# BD0005.net
KiCad netlist of a schematic drawn in EAGLE
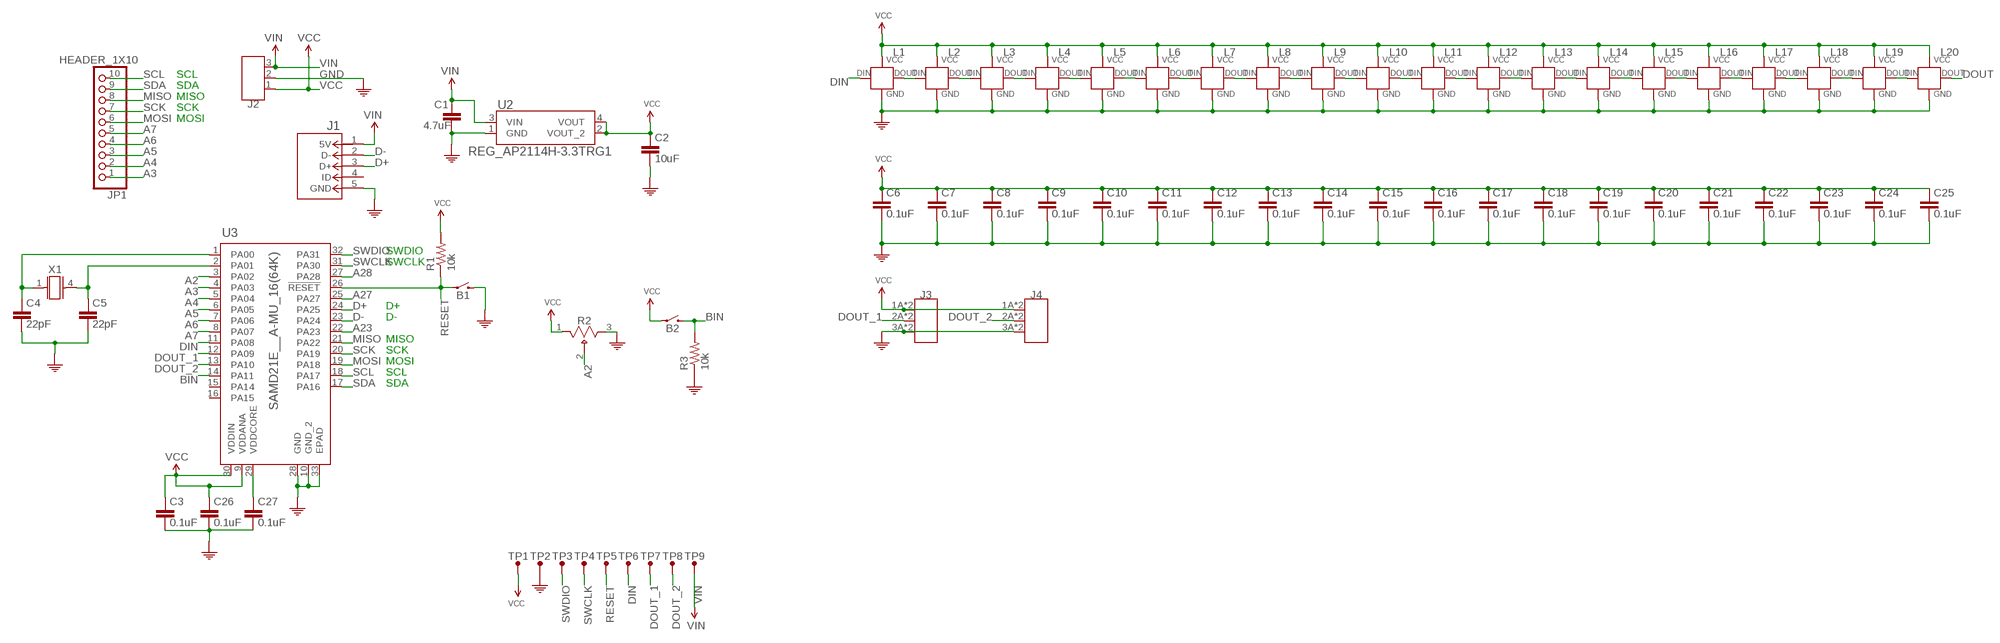
[diagram p0: schematic, sheet 1]

(export (version "E")
  (design (tool "Eeschema 10.0.6"))
  (components
    (comp (ref "B1")
      (value "SWITCH_EVQ-P7A01P")
      (footprint "eagle-import:4-SMD_BUTTON")
      (libsource (lib "eagle-import") (part "SWITCH_EVQ-P7A01P"))
    )
    (comp (ref "B2")
      (value "SWITCH_EVQ-P7A01P")
      (footprint "eagle-import:4-SMD_BUTTON")
      (libsource (lib "eagle-import") (part "SWITCH_EVQ-P7A01P"))
    )
    (comp (ref "C1")
      (value "4.7uF")
      (footprint "eagle-import:0402")
      (libsource (lib "eagle-import") (part "CAPACITOR-0402"))
    )
    (comp (ref "C2")
      (value "10uF")
      (footprint "eagle-import:0402")
      (libsource (lib "eagle-import") (part "CAPACITOR-0402"))
    )
    (comp (ref "C3")
      (value "0.1uF")
      (footprint "eagle-import:0402")
      (libsource (lib "eagle-import") (part "CAPACITOR-0402"))
    )
    (comp (ref "C4")
      (value "22pF")
      (footprint "eagle-import:0402")
      (libsource (lib "eagle-import") (part "CAPACITOR-0402"))
    )
    (comp (ref "C5")
      (value "22pF")
      (footprint "eagle-import:0402")
      (libsource (lib "eagle-import") (part "CAPACITOR-0402"))
    )
    (comp (ref "C6")
      (value "0.1uF")
      (footprint "eagle-import:0402")
      (libsource (lib "eagle-import") (part "CAPACITOR-0402"))
    )
    (comp (ref "C7")
      (value "0.1uF")
      (footprint "eagle-import:0402")
      (libsource (lib "eagle-import") (part "CAPACITOR-0402"))
    )
    (comp (ref "C8")
      (value "0.1uF")
      (footprint "eagle-import:0402")
      (libsource (lib "eagle-import") (part "CAPACITOR-0402"))
    )
    (comp (ref "C9")
      (value "0.1uF")
      (footprint "eagle-import:0402")
      (libsource (lib "eagle-import") (part "CAPACITOR-0402"))
    )
    (comp (ref "C10")
      (value "0.1uF")
      (footprint "eagle-import:0402")
      (libsource (lib "eagle-import") (part "CAPACITOR-0402"))
    )
    (comp (ref "C11")
      (value "0.1uF")
      (footprint "eagle-import:0402")
      (libsource (lib "eagle-import") (part "CAPACITOR-0402"))
    )
    (comp (ref "C12")
      (value "0.1uF")
      (footprint "eagle-import:0402")
      (libsource (lib "eagle-import") (part "CAPACITOR-0402"))
    )
    (comp (ref "C13")
      (value "0.1uF")
      (footprint "eagle-import:0402")
      (libsource (lib "eagle-import") (part "CAPACITOR-0402"))
    )
    (comp (ref "C14")
      (value "0.1uF")
      (footprint "eagle-import:0402")
      (libsource (lib "eagle-import") (part "CAPACITOR-0402"))
    )
    (comp (ref "C15")
      (value "0.1uF")
      (footprint "eagle-import:0402")
      (libsource (lib "eagle-import") (part "CAPACITOR-0402"))
    )
    (comp (ref "C16")
      (value "0.1uF")
      (footprint "eagle-import:0402")
      (libsource (lib "eagle-import") (part "CAPACITOR-0402"))
    )
    (comp (ref "C17")
      (value "0.1uF")
      (footprint "eagle-import:0402")
      (libsource (lib "eagle-import") (part "CAPACITOR-0402"))
    )
    (comp (ref "C18")
      (value "0.1uF")
      (footprint "eagle-import:0402")
      (libsource (lib "eagle-import") (part "CAPACITOR-0402"))
    )
    (comp (ref "C19")
      (value "0.1uF")
      (footprint "eagle-import:0402")
      (libsource (lib "eagle-import") (part "CAPACITOR-0402"))
    )
    (comp (ref "C20")
      (value "0.1uF")
      (footprint "eagle-import:0402")
      (libsource (lib "eagle-import") (part "CAPACITOR-0402"))
    )
    (comp (ref "C21")
      (value "0.1uF")
      (footprint "eagle-import:0402")
      (libsource (lib "eagle-import") (part "CAPACITOR-0402"))
    )
    (comp (ref "C22")
      (value "0.1uF")
      (footprint "eagle-import:0402")
      (libsource (lib "eagle-import") (part "CAPACITOR-0402"))
    )
    (comp (ref "C23")
      (value "0.1uF")
      (footprint "eagle-import:0402")
      (libsource (lib "eagle-import") (part "CAPACITOR-0402"))
    )
    (comp (ref "C24")
      (value "0.1uF")
      (footprint "eagle-import:0402")
      (libsource (lib "eagle-import") (part "CAPACITOR-0402"))
    )
    (comp (ref "C25")
      (value "0.1uF")
      (footprint "eagle-import:0402")
      (libsource (lib "eagle-import") (part "CAPACITOR-0402"))
    )
    (comp (ref "C26")
      (value "0.1uF")
      (footprint "eagle-import:0402")
      (libsource (lib "eagle-import") (part "CAPACITOR-0402"))
    )
    (comp (ref "C27")
      (value "0.1uF")
      (footprint "eagle-import:0402")
      (libsource (lib "eagle-import") (part "CAPACITOR-0402"))
    )
    (comp (ref "J1")
      (value "CONN_MICROUSB_FEMALE")
      (footprint "eagle-import:CON00679_5")
      (libsource (lib "eagle-import") (part "CONN_MICROUSB_FEMALE"))
    )
    (comp (ref "J2")
      (value "HEADER_1X3")
      (footprint "eagle-import:1X03-CLEANBIG")
      (libsource (lib "eagle-import") (part "HEADER_1X3"))
    )
    (comp (ref "J3")
      (value "HEADER_1X3FEMALE")
      (footprint "eagle-import:F3SMD_RIGHTANGLE")
      (libsource (lib "eagle-import") (part "HEADER_1X3FEMALE"))
    )
    (comp (ref "J4")
      (value "HEADER_1X3FEMALE")
      (footprint "eagle-import:F3SMD_RIGHTANGLE")
      (libsource (lib "eagle-import") (part "HEADER_1X3FEMALE"))
    )
    (comp (ref "JP1")
      (value "HEADER_1X10")
      (footprint "eagle-import:1X10-BIG")
      (libsource (lib "eagle-import") (part "HEADER_1X10"))
    )
    (comp (ref "L1")
      (value "WS2812B-B")
      (footprint "eagle-import:SK6812-B")
      (libsource (lib "eagle-import") (part "WS2812B-B"))
    )
    (comp (ref "L2")
      (value "WS2812B-B")
      (footprint "eagle-import:SK6812-B")
      (libsource (lib "eagle-import") (part "WS2812B-B"))
    )
    (comp (ref "L3")
      (value "WS2812B-B")
      (footprint "eagle-import:SK6812-B")
      (libsource (lib "eagle-import") (part "WS2812B-B"))
    )
    (comp (ref "L4")
      (value "WS2812B-B")
      (footprint "eagle-import:SK6812-B")
      (libsource (lib "eagle-import") (part "WS2812B-B"))
    )
    (comp (ref "L5")
      (value "WS2812B-B")
      (footprint "eagle-import:SK6812-B")
      (libsource (lib "eagle-import") (part "WS2812B-B"))
    )
    (comp (ref "L6")
      (value "WS2812B-B")
      (footprint "eagle-import:SK6812-B")
      (libsource (lib "eagle-import") (part "WS2812B-B"))
    )
    (comp (ref "L7")
      (value "WS2812B-B")
      (footprint "eagle-import:SK6812-B")
      (libsource (lib "eagle-import") (part "WS2812B-B"))
    )
    (comp (ref "L8")
      (value "WS2812B-B")
      (footprint "eagle-import:SK6812-B")
      (libsource (lib "eagle-import") (part "WS2812B-B"))
    )
    (comp (ref "L9")
      (value "WS2812B-B")
      (footprint "eagle-import:SK6812-B")
      (libsource (lib "eagle-import") (part "WS2812B-B"))
    )
    (comp (ref "L10")
      (value "WS2812B-B")
      (footprint "eagle-import:SK6812-B")
      (libsource (lib "eagle-import") (part "WS2812B-B"))
    )
    (comp (ref "L11")
      (value "WS2812B-B")
      (footprint "eagle-import:SK6812-B")
      (libsource (lib "eagle-import") (part "WS2812B-B"))
    )
    (comp (ref "L12")
      (value "WS2812B-B")
      (footprint "eagle-import:SK6812-B")
      (libsource (lib "eagle-import") (part "WS2812B-B"))
    )
    (comp (ref "L13")
      (value "WS2812B-B")
      (footprint "eagle-import:SK6812-B")
      (libsource (lib "eagle-import") (part "WS2812B-B"))
    )
    (comp (ref "L14")
      (value "WS2812B-B")
      (footprint "eagle-import:SK6812-B")
      (libsource (lib "eagle-import") (part "WS2812B-B"))
    )
    (comp (ref "L15")
      (value "WS2812B-B")
      (footprint "eagle-import:SK6812-B")
      (libsource (lib "eagle-import") (part "WS2812B-B"))
    )
    (comp (ref "L16")
      (value "WS2812B-B")
      (footprint "eagle-import:SK6812-B")
      (libsource (lib "eagle-import") (part "WS2812B-B"))
    )
    (comp (ref "L17")
      (value "WS2812B-B")
      (footprint "eagle-import:SK6812-B")
      (libsource (lib "eagle-import") (part "WS2812B-B"))
    )
    (comp (ref "L18")
      (value "WS2812B-B")
      (footprint "eagle-import:SK6812-B")
      (libsource (lib "eagle-import") (part "WS2812B-B"))
    )
    (comp (ref "L19")
      (value "WS2812B-B")
      (footprint "eagle-import:SK6812-B")
      (libsource (lib "eagle-import") (part "WS2812B-B"))
    )
    (comp (ref "L20")
      (value "WS2812B-B")
      (footprint "eagle-import:SK6812-B")
      (libsource (lib "eagle-import") (part "WS2812B-B"))
    )
    (comp (ref "R1")
      (value "10k")
      (footprint "eagle-import:0402")
      (libsource (lib "eagle-import") (part "RESISTOR-0402"))
    )
    (comp (ref "R2")
      (value "POT_THUMBWHEEL_3352T-1-104LF")
      (footprint "eagle-import:THUMBWHEEL")
      (libsource (lib "eagle-import") (part "POT_THUMBWHEEL_3352T-1-104LF"))
    )
    (comp (ref "R3")
      (value "10k")
      (footprint "eagle-import:0402")
      (libsource (lib "eagle-import") (part "RESISTOR-0402"))
    )
    (comp (ref "TP1")
      (value "VCC")
      (footprint "eagle-import:TEST_POINT")
      (libsource (lib "eagle-import") (part "TEST_POINT"))
    )
    (comp (ref "TP2")
      (value "GND")
      (footprint "eagle-import:TEST_POINT")
      (libsource (lib "eagle-import") (part "TEST_POINT"))
    )
    (comp (ref "TP3")
      (value "DIO")
      (footprint "eagle-import:TEST_POINT")
      (libsource (lib "eagle-import") (part "TEST_POINT"))
    )
    (comp (ref "TP4")
      (value "CLK")
      (footprint "eagle-import:TEST_POINT")
      (libsource (lib "eagle-import") (part "TEST_POINT"))
    )
    (comp (ref "TP5")
      (value "RST")
      (footprint "eagle-import:TEST_POINT")
      (libsource (lib "eagle-import") (part "TEST_POINT"))
    )
    (comp (ref "TP6")
      (value "DIN")
      (footprint "eagle-import:TEST_POINT")
      (libsource (lib "eagle-import") (part "TEST_POINT"))
    )
    (comp (ref "TP7")
      (value "DO1")
      (footprint "eagle-import:TEST_POINT")
      (libsource (lib "eagle-import") (part "TEST_POINT"))
    )
    (comp (ref "TP8")
      (value "DO2")
      (footprint "eagle-import:TEST_POINT")
      (libsource (lib "eagle-import") (part "TEST_POINT"))
    )
    (comp (ref "TP9")
      (value "VIN")
      (footprint "eagle-import:TEST_POINT")
      (libsource (lib "eagle-import") (part "TEST_POINT"))
    )
    (comp (ref "U2")
      (value "REG_AP2114H-3.3TRG1")
      (footprint "eagle-import:SOT-223")
      (libsource (lib "eagle-import") (part "REG_AP2114H-3.3TRG1"))
    )
    (comp (ref "U3")
      (value "SAMD21E__A-MU_16(64K)")
      (footprint "eagle-import:QFN32_5X5MC_MCH")
      (libsource (lib "eagle-import") (part "SAMD21E__A-MU_16(64K)"))
    )
    (comp (ref "X1")
      (value "XTAL_MC-146-32.7680JKA-A0:ROHS")
      (footprint "eagle-import:4-SMD_FLAT_LEADS")
      (libsource (lib "eagle-import") (part "XTAL_MC-146-32.7680JKA-A0{colon}ROHS"))
    )
  )
  (nets
    (net (code "1") (name "/A2") (class "Default")
      (node (ref "R2") (pin "2") (pinfunction "P$2_2") (pintype "bidirectional"))
      (node (ref "U3") (pin "3") (pinfunction "PA02_3") (pintype "bidirectional"))
    )
    (net (code "2") (name "/A3") (class "Default")
      (node (ref "JP1") (pin "1") (pinfunction "1_1") (pintype "passive"))
      (node (ref "U3") (pin "4") (pinfunction "PA03_4") (pintype "bidirectional"))
    )
    (net (code "3") (name "/A4") (class "Default")
      (node (ref "JP1") (pin "2") (pinfunction "2_2") (pintype "passive"))
      (node (ref "U3") (pin "5") (pinfunction "PA04_5") (pintype "bidirectional"))
    )
    (net (code "4") (name "/A5") (class "Default")
      (node (ref "JP1") (pin "3") (pinfunction "3_3") (pintype "passive"))
      (node (ref "U3") (pin "6") (pinfunction "PA05_6") (pintype "bidirectional"))
    )
    (net (code "5") (name "/A6") (class "Default")
      (node (ref "JP1") (pin "4") (pinfunction "4_4") (pintype "passive"))
      (node (ref "U3") (pin "7") (pinfunction "PA06_7") (pintype "bidirectional"))
    )
    (net (code "6") (name "/A7") (class "Default")
      (node (ref "JP1") (pin "5") (pinfunction "5_5") (pintype "passive"))
      (node (ref "U3") (pin "8") (pinfunction "PA07_8") (pintype "bidirectional"))
    )
    (net (code "7") (name "/A23") (class "Default")
      (node (ref "U3") (pin "22") (pinfunction "PA23_22") (pintype "bidirectional"))
    )
    (net (code "8") (name "/A27") (class "Default")
      (node (ref "U3") (pin "25") (pinfunction "PA27_25") (pintype "bidirectional"))
    )
    (net (code "9") (name "/A28") (class "Default")
      (node (ref "U3") (pin "27") (pinfunction "PA28_27") (pintype "bidirectional"))
    )
    (net (code "10") (name "/BIN") (class "Default")
      (node (ref "B2") (pin "2A") (pinfunction "P$2_2A") (pintype "bidirectional"))
      (node (ref "B2") (pin "2B") (pinfunction "P$2_2B") (pintype "bidirectional"))
      (node (ref "R3") (pin "P$2") (pinfunction "2_P$2") (pintype "passive"))
      (node (ref "U3") (pin "14") (pinfunction "PA11_14") (pintype "bidirectional"))
    )
    (net (code "11") (name "/D+") (class "Default")
      (node (ref "J1") (pin "3") (pinfunction "D+_3") (pintype "passive"))
      (node (ref "U3") (pin "24") (pinfunction "PA25_24") (pintype "bidirectional"))
    )
    (net (code "12") (name "/D-") (class "Default")
      (node (ref "J1") (pin "2") (pinfunction "D-_2") (pintype "passive"))
      (node (ref "U3") (pin "23") (pinfunction "PA24_23") (pintype "bidirectional"))
    )
    (net (code "13") (name "/DIN") (class "Default")
      (node (ref "L1") (pin "2") (pinfunction "DIN_2") (pintype "bidirectional"))
      (node (ref "TP6") (pin "P$1") (pinfunction "P$1_P$1") (pintype "input"))
      (node (ref "U3") (pin "11") (pinfunction "PA08_11") (pintype "bidirectional"))
    )
    (net (code "14") (name "/DOUT") (class "Default")
      (node (ref "L20") (pin "4") (pinfunction "DOUT_4") (pintype "bidirectional"))
    )
    (net (code "15") (name "/DOUT_1") (class "Default")
      (node (ref "J3") (pin "2A") (pinfunction "P$2_2A") (pintype "bidirectional"))
      (node (ref "J3") (pin "2B") (pinfunction "P$2_2B") (pintype "bidirectional"))
      (node (ref "TP7") (pin "P$1") (pinfunction "P$1_P$1") (pintype "input"))
      (node (ref "U3") (pin "12") (pinfunction "PA09_12") (pintype "bidirectional"))
    )
    (net (code "16") (name "/DOUT_2") (class "Default")
      (node (ref "J4") (pin "2A") (pinfunction "P$2_2A") (pintype "bidirectional"))
      (node (ref "J4") (pin "2B") (pinfunction "P$2_2B") (pintype "bidirectional"))
      (node (ref "TP8") (pin "P$1") (pinfunction "P$1_P$1") (pintype "input"))
      (node (ref "U3") (pin "13") (pinfunction "PA10_13") (pintype "bidirectional"))
    )
    (net (code "17") (name "/MISO") (class "Default")
      (node (ref "JP1") (pin "8") (pinfunction "8_8") (pintype "passive"))
      (node (ref "U3") (pin "21") (pinfunction "PA22_21") (pintype "bidirectional"))
    )
    (net (code "18") (name "/MOSI") (class "Default")
      (node (ref "JP1") (pin "6") (pinfunction "6_6") (pintype "passive"))
      (node (ref "U3") (pin "19") (pinfunction "PA18_19") (pintype "bidirectional"))
    )
    (net (code "19") (name "/RESET") (class "Default")
      (node (ref "B1") (pin "1A") (pinfunction "P$1_1A") (pintype "bidirectional"))
      (node (ref "B1") (pin "1B") (pinfunction "P$1_1B") (pintype "bidirectional"))
      (node (ref "R1") (pin "P$1") (pinfunction "1_P$1") (pintype "passive"))
      (node (ref "TP5") (pin "P$1") (pinfunction "P$1_P$1") (pintype "input"))
      (node (ref "U3") (pin "26") (pinfunction "~{RESET}_26") (pintype "passive"))
    )
    (net (code "20") (name "/SCK") (class "Default")
      (node (ref "JP1") (pin "7") (pinfunction "7_7") (pintype "passive"))
      (node (ref "U3") (pin "20") (pinfunction "PA19_20") (pintype "bidirectional"))
    )
    (net (code "21") (name "/SCL") (class "Default")
      (node (ref "JP1") (pin "10") (pinfunction "10_10") (pintype "passive"))
      (node (ref "U3") (pin "18") (pinfunction "PA17_18") (pintype "bidirectional"))
    )
    (net (code "22") (name "/SDA") (class "Default")
      (node (ref "JP1") (pin "9") (pinfunction "9_9") (pintype "passive"))
      (node (ref "U3") (pin "17") (pinfunction "PA16_17") (pintype "bidirectional"))
    )
    (net (code "23") (name "/SWCLK") (class "Default")
      (node (ref "TP4") (pin "P$1") (pinfunction "P$1_P$1") (pintype "input"))
      (node (ref "U3") (pin "31") (pinfunction "PA30_31") (pintype "bidirectional"))
    )
    (net (code "24") (name "/SWDIO") (class "Default")
      (node (ref "TP3") (pin "P$1") (pinfunction "P$1_P$1") (pintype "input"))
      (node (ref "U3") (pin "32") (pinfunction "PA31_32") (pintype "bidirectional"))
    )
    (net (code "25") (name "GND") (class "Default")
      (node (ref "B1") (pin "2A") (pinfunction "P$2_2A") (pintype "bidirectional"))
      (node (ref "B1") (pin "2B") (pinfunction "P$2_2B") (pintype "bidirectional"))
      (node (ref "C1") (pin "P$2") (pinfunction "2_P$2") (pintype "passive"))
      (node (ref "C10") (pin "P$2") (pinfunction "2_P$2") (pintype "passive"))
      (node (ref "C11") (pin "P$2") (pinfunction "2_P$2") (pintype "passive"))
      (node (ref "C12") (pin "P$2") (pinfunction "2_P$2") (pintype "passive"))
      (node (ref "C13") (pin "P$2") (pinfunction "2_P$2") (pintype "passive"))
      (node (ref "C14") (pin "P$2") (pinfunction "2_P$2") (pintype "passive"))
      (node (ref "C15") (pin "P$2") (pinfunction "2_P$2") (pintype "passive"))
      (node (ref "C16") (pin "P$2") (pinfunction "2_P$2") (pintype "passive"))
      (node (ref "C17") (pin "P$2") (pinfunction "2_P$2") (pintype "passive"))
      (node (ref "C18") (pin "P$2") (pinfunction "2_P$2") (pintype "passive"))
      (node (ref "C19") (pin "P$2") (pinfunction "2_P$2") (pintype "passive"))
      (node (ref "C2") (pin "P$2") (pinfunction "2_P$2") (pintype "passive"))
      (node (ref "C20") (pin "P$2") (pinfunction "2_P$2") (pintype "passive"))
      (node (ref "C21") (pin "P$2") (pinfunction "2_P$2") (pintype "passive"))
      (node (ref "C22") (pin "P$2") (pinfunction "2_P$2") (pintype "passive"))
      (node (ref "C23") (pin "P$2") (pinfunction "2_P$2") (pintype "passive"))
      (node (ref "C24") (pin "P$2") (pinfunction "2_P$2") (pintype "passive"))
      (node (ref "C25") (pin "P$2") (pinfunction "2_P$2") (pintype "passive"))
      (node (ref "C26") (pin "P$2") (pinfunction "2_P$2") (pintype "passive"))
      (node (ref "C27") (pin "P$2") (pinfunction "2_P$2") (pintype "passive"))
      (node (ref "C3") (pin "P$2") (pinfunction "2_P$2") (pintype "passive"))
      (node (ref "C4") (pin "P$2") (pinfunction "2_P$2") (pintype "passive"))
      (node (ref "C5") (pin "P$2") (pinfunction "2_P$2") (pintype "passive"))
      (node (ref "C6") (pin "P$2") (pinfunction "2_P$2") (pintype "passive"))
      (node (ref "C7") (pin "P$2") (pinfunction "2_P$2") (pintype "passive"))
      (node (ref "C8") (pin "P$2") (pinfunction "2_P$2") (pintype "passive"))
      (node (ref "C9") (pin "P$2") (pinfunction "2_P$2") (pintype "passive"))
      (node (ref "J1") (pin "5") (pinfunction "GND_5") (pintype "passive"))
      (node (ref "J2") (pin "2") (pinfunction "P$2_2") (pintype "bidirectional"))
      (node (ref "J3") (pin "3A") (pinfunction "P$3_3A") (pintype "bidirectional"))
      (node (ref "J3") (pin "3B") (pinfunction "P$3_3B") (pintype "bidirectional"))
      (node (ref "J4") (pin "3A") (pinfunction "P$3_3A") (pintype "bidirectional"))
      (node (ref "J4") (pin "3B") (pinfunction "P$3_3B") (pintype "bidirectional"))
      (node (ref "L1") (pin "1") (pinfunction "VSS_1") (pintype "bidirectional"))
      (node (ref "L10") (pin "1") (pinfunction "VSS_1") (pintype "bidirectional"))
      (node (ref "L11") (pin "1") (pinfunction "VSS_1") (pintype "bidirectional"))
      (node (ref "L12") (pin "1") (pinfunction "VSS_1") (pintype "bidirectional"))
      (node (ref "L13") (pin "1") (pinfunction "VSS_1") (pintype "bidirectional"))
      (node (ref "L14") (pin "1") (pinfunction "VSS_1") (pintype "bidirectional"))
      (node (ref "L15") (pin "1") (pinfunction "VSS_1") (pintype "bidirectional"))
      (node (ref "L16") (pin "1") (pinfunction "VSS_1") (pintype "bidirectional"))
      (node (ref "L17") (pin "1") (pinfunction "VSS_1") (pintype "bidirectional"))
      (node (ref "L18") (pin "1") (pinfunction "VSS_1") (pintype "bidirectional"))
      (node (ref "L19") (pin "1") (pinfunction "VSS_1") (pintype "bidirectional"))
      (node (ref "L2") (pin "1") (pinfunction "VSS_1") (pintype "bidirectional"))
      (node (ref "L20") (pin "1") (pinfunction "VSS_1") (pintype "bidirectional"))
      (node (ref "L3") (pin "1") (pinfunction "VSS_1") (pintype "bidirectional"))
      (node (ref "L4") (pin "1") (pinfunction "VSS_1") (pintype "bidirectional"))
      (node (ref "L5") (pin "1") (pinfunction "VSS_1") (pintype "bidirectional"))
      (node (ref "L6") (pin "1") (pinfunction "VSS_1") (pintype "bidirectional"))
      (node (ref "L7") (pin "1") (pinfunction "VSS_1") (pintype "bidirectional"))
      (node (ref "L8") (pin "1") (pinfunction "VSS_1") (pintype "bidirectional"))
      (node (ref "L9") (pin "1") (pinfunction "VSS_1") (pintype "bidirectional"))
      (node (ref "R2") (pin "3") (pinfunction "P$3_3") (pintype "bidirectional"))
      (node (ref "R3") (pin "P$1") (pinfunction "1_P$1") (pintype "passive"))
      (node (ref "TP2") (pin "P$1") (pinfunction "P$1_P$1") (pintype "input"))
      (node (ref "U2") (pin "1") (pinfunction "GND_1") (pintype "passive"))
      (node (ref "U3") (pin "10") (pinfunction "GND_2_10") (pintype "passive"))
      (node (ref "U3") (pin "28") (pinfunction "GND_28") (pintype "passive"))
      (node (ref "U3") (pin "33") (pinfunction "EPAD_33") (pintype "passive"))
    )
    (net (code "26") (name "Net-(C4-1)") (class "Default")
      (node (ref "C4") (pin "P$1") (pinfunction "1_P$1") (pintype "passive"))
      (node (ref "U3") (pin "1") (pinfunction "PA00_1") (pintype "bidirectional"))
      (node (ref "X1") (pin "1") (pinfunction "P$1_1") (pintype "bidirectional"))
    )
    (net (code "27") (name "Net-(C5-1)") (class "Default")
      (node (ref "C5") (pin "P$1") (pinfunction "1_P$1") (pintype "passive"))
      (node (ref "U3") (pin "2") (pinfunction "PA01_2") (pintype "bidirectional"))
      (node (ref "X1") (pin "4") (pinfunction "P$2_4") (pintype "bidirectional"))
    )
    (net (code "28") (name "Net-(C27-1)") (class "Default")
      (node (ref "C27") (pin "P$1") (pinfunction "1_P$1") (pintype "passive"))
      (node (ref "U3") (pin "29") (pinfunction "VDDCORE_29") (pintype "power_in"))
    )
    (net (code "29") (name "Net-(L1-DOUT)") (class "Default")
      (node (ref "L1") (pin "4") (pinfunction "DOUT_4") (pintype "bidirectional"))
      (node (ref "L2") (pin "2") (pinfunction "DIN_2") (pintype "bidirectional"))
    )
    (net (code "30") (name "Net-(L2-DOUT)") (class "Default")
      (node (ref "L2") (pin "4") (pinfunction "DOUT_4") (pintype "bidirectional"))
      (node (ref "L3") (pin "2") (pinfunction "DIN_2") (pintype "bidirectional"))
    )
    (net (code "31") (name "Net-(L3-DOUT)") (class "Default")
      (node (ref "L3") (pin "4") (pinfunction "DOUT_4") (pintype "bidirectional"))
      (node (ref "L4") (pin "2") (pinfunction "DIN_2") (pintype "bidirectional"))
    )
    (net (code "32") (name "Net-(L4-DOUT)") (class "Default")
      (node (ref "L4") (pin "4") (pinfunction "DOUT_4") (pintype "bidirectional"))
      (node (ref "L5") (pin "2") (pinfunction "DIN_2") (pintype "bidirectional"))
    )
    (net (code "33") (name "Net-(L5-DOUT)") (class "Default")
      (node (ref "L5") (pin "4") (pinfunction "DOUT_4") (pintype "bidirectional"))
      (node (ref "L6") (pin "2") (pinfunction "DIN_2") (pintype "bidirectional"))
    )
    (net (code "34") (name "Net-(L6-DOUT)") (class "Default")
      (node (ref "L6") (pin "4") (pinfunction "DOUT_4") (pintype "bidirectional"))
      (node (ref "L7") (pin "2") (pinfunction "DIN_2") (pintype "bidirectional"))
    )
    (net (code "35") (name "Net-(L7-DOUT)") (class "Default")
      (node (ref "L7") (pin "4") (pinfunction "DOUT_4") (pintype "bidirectional"))
      (node (ref "L8") (pin "2") (pinfunction "DIN_2") (pintype "bidirectional"))
    )
    (net (code "36") (name "Net-(L8-DOUT)") (class "Default")
      (node (ref "L8") (pin "4") (pinfunction "DOUT_4") (pintype "bidirectional"))
      (node (ref "L9") (pin "2") (pinfunction "DIN_2") (pintype "bidirectional"))
    )
    (net (code "37") (name "Net-(L10-DIN)") (class "Default")
      (node (ref "L10") (pin "2") (pinfunction "DIN_2") (pintype "bidirectional"))
      (node (ref "L9") (pin "4") (pinfunction "DOUT_4") (pintype "bidirectional"))
    )
    (net (code "38") (name "Net-(L10-DOUT)") (class "Default")
      (node (ref "L10") (pin "4") (pinfunction "DOUT_4") (pintype "bidirectional"))
      (node (ref "L11") (pin "2") (pinfunction "DIN_2") (pintype "bidirectional"))
    )
    (net (code "39") (name "Net-(L11-DOUT)") (class "Default")
      (node (ref "L11") (pin "4") (pinfunction "DOUT_4") (pintype "bidirectional"))
      (node (ref "L12") (pin "2") (pinfunction "DIN_2") (pintype "bidirectional"))
    )
    (net (code "40") (name "Net-(L12-DOUT)") (class "Default")
      (node (ref "L12") (pin "4") (pinfunction "DOUT_4") (pintype "bidirectional"))
      (node (ref "L13") (pin "2") (pinfunction "DIN_2") (pintype "bidirectional"))
    )
    (net (code "41") (name "Net-(L13-DOUT)") (class "Default")
      (node (ref "L13") (pin "4") (pinfunction "DOUT_4") (pintype "bidirectional"))
      (node (ref "L14") (pin "2") (pinfunction "DIN_2") (pintype "bidirectional"))
    )
    (net (code "42") (name "Net-(L14-DOUT)") (class "Default")
      (node (ref "L14") (pin "4") (pinfunction "DOUT_4") (pintype "bidirectional"))
      (node (ref "L15") (pin "2") (pinfunction "DIN_2") (pintype "bidirectional"))
    )
    (net (code "43") (name "Net-(L15-DOUT)") (class "Default")
      (node (ref "L15") (pin "4") (pinfunction "DOUT_4") (pintype "bidirectional"))
      (node (ref "L16") (pin "2") (pinfunction "DIN_2") (pintype "bidirectional"))
    )
    (net (code "44") (name "Net-(L16-DOUT)") (class "Default")
      (node (ref "L16") (pin "4") (pinfunction "DOUT_4") (pintype "bidirectional"))
      (node (ref "L17") (pin "2") (pinfunction "DIN_2") (pintype "bidirectional"))
    )
    (net (code "45") (name "Net-(L17-DOUT)") (class "Default")
      (node (ref "L17") (pin "4") (pinfunction "DOUT_4") (pintype "bidirectional"))
      (node (ref "L18") (pin "2") (pinfunction "DIN_2") (pintype "bidirectional"))
    )
    (net (code "46") (name "Net-(L18-DOUT)") (class "Default")
      (node (ref "L18") (pin "4") (pinfunction "DOUT_4") (pintype "bidirectional"))
      (node (ref "L19") (pin "2") (pinfunction "DIN_2") (pintype "bidirectional"))
    )
    (net (code "47") (name "Net-(L19-DOUT)") (class "Default")
      (node (ref "L19") (pin "4") (pinfunction "DOUT_4") (pintype "bidirectional"))
      (node (ref "L20") (pin "2") (pinfunction "DIN_2") (pintype "bidirectional"))
    )
    (net (code "48") (name "VCC") (class "Default")
      (node (ref "B2") (pin "1A") (pinfunction "P$1_1A") (pintype "bidirectional"))
      (node (ref "B2") (pin "1B") (pinfunction "P$1_1B") (pintype "bidirectional"))
      (node (ref "C10") (pin "P$1") (pinfunction "1_P$1") (pintype "passive"))
      (node (ref "C11") (pin "P$1") (pinfunction "1_P$1") (pintype "passive"))
      (node (ref "C12") (pin "P$1") (pinfunction "1_P$1") (pintype "passive"))
      (node (ref "C13") (pin "P$1") (pinfunction "1_P$1") (pintype "passive"))
      (node (ref "C14") (pin "P$1") (pinfunction "1_P$1") (pintype "passive"))
      (node (ref "C15") (pin "P$1") (pinfunction "1_P$1") (pintype "passive"))
      (node (ref "C16") (pin "P$1") (pinfunction "1_P$1") (pintype "passive"))
      (node (ref "C17") (pin "P$1") (pinfunction "1_P$1") (pintype "passive"))
      (node (ref "C18") (pin "P$1") (pinfunction "1_P$1") (pintype "passive"))
      (node (ref "C19") (pin "P$1") (pinfunction "1_P$1") (pintype "passive"))
      (node (ref "C2") (pin "P$1") (pinfunction "1_P$1") (pintype "passive"))
      (node (ref "C20") (pin "P$1") (pinfunction "1_P$1") (pintype "passive"))
      (node (ref "C21") (pin "P$1") (pinfunction "1_P$1") (pintype "passive"))
      (node (ref "C22") (pin "P$1") (pinfunction "1_P$1") (pintype "passive"))
      (node (ref "C23") (pin "P$1") (pinfunction "1_P$1") (pintype "passive"))
      (node (ref "C24") (pin "P$1") (pinfunction "1_P$1") (pintype "passive"))
      (node (ref "C25") (pin "P$1") (pinfunction "1_P$1") (pintype "passive"))
      (node (ref "C26") (pin "P$1") (pinfunction "1_P$1") (pintype "passive"))
      (node (ref "C3") (pin "P$1") (pinfunction "1_P$1") (pintype "passive"))
      (node (ref "C6") (pin "P$1") (pinfunction "1_P$1") (pintype "passive"))
      (node (ref "C7") (pin "P$1") (pinfunction "1_P$1") (pintype "passive"))
      (node (ref "C8") (pin "P$1") (pinfunction "1_P$1") (pintype "passive"))
      (node (ref "C9") (pin "P$1") (pinfunction "1_P$1") (pintype "passive"))
      (node (ref "J2") (pin "1") (pinfunction "P$1_1") (pintype "bidirectional"))
      (node (ref "J3") (pin "1A") (pinfunction "P$1_1A") (pintype "bidirectional"))
      (node (ref "J3") (pin "1B") (pinfunction "P$1_1B") (pintype "bidirectional"))
      (node (ref "J4") (pin "1A") (pinfunction "P$1_1A") (pintype "bidirectional"))
      (node (ref "J4") (pin "1B") (pinfunction "P$1_1B") (pintype "bidirectional"))
      (node (ref "L1") (pin "3") (pinfunction "VDD_3") (pintype "bidirectional"))
      (node (ref "L10") (pin "3") (pinfunction "VDD_3") (pintype "bidirectional"))
      (node (ref "L11") (pin "3") (pinfunction "VDD_3") (pintype "bidirectional"))
      (node (ref "L12") (pin "3") (pinfunction "VDD_3") (pintype "bidirectional"))
      (node (ref "L13") (pin "3") (pinfunction "VDD_3") (pintype "bidirectional"))
      (node (ref "L14") (pin "3") (pinfunction "VDD_3") (pintype "bidirectional"))
      (node (ref "L15") (pin "3") (pinfunction "VDD_3") (pintype "bidirectional"))
      (node (ref "L16") (pin "3") (pinfunction "VDD_3") (pintype "bidirectional"))
      (node (ref "L17") (pin "3") (pinfunction "VDD_3") (pintype "bidirectional"))
      (node (ref "L18") (pin "3") (pinfunction "VDD_3") (pintype "bidirectional"))
      (node (ref "L19") (pin "3") (pinfunction "VDD_3") (pintype "bidirectional"))
      (node (ref "L2") (pin "3") (pinfunction "VDD_3") (pintype "bidirectional"))
      (node (ref "L20") (pin "3") (pinfunction "VDD_3") (pintype "bidirectional"))
      (node (ref "L3") (pin "3") (pinfunction "VDD_3") (pintype "bidirectional"))
      (node (ref "L4") (pin "3") (pinfunction "VDD_3") (pintype "bidirectional"))
      (node (ref "L5") (pin "3") (pinfunction "VDD_3") (pintype "bidirectional"))
      (node (ref "L6") (pin "3") (pinfunction "VDD_3") (pintype "bidirectional"))
      (node (ref "L7") (pin "3") (pinfunction "VDD_3") (pintype "bidirectional"))
      (node (ref "L8") (pin "3") (pinfunction "VDD_3") (pintype "bidirectional"))
      (node (ref "L9") (pin "3") (pinfunction "VDD_3") (pintype "bidirectional"))
      (node (ref "R1") (pin "P$2") (pinfunction "2_P$2") (pintype "passive"))
      (node (ref "R2") (pin "1") (pinfunction "P$1_1") (pintype "bidirectional"))
      (node (ref "TP1") (pin "P$1") (pinfunction "P$1_P$1") (pintype "input"))
      (node (ref "U2") (pin "2") (pinfunction "VOUT_2_2") (pintype "output"))
      (node (ref "U2") (pin "4") (pinfunction "VOUT_4") (pintype "output"))
      (node (ref "U3") (pin "30") (pinfunction "VDDIN_30") (pintype "power_in"))
      (node (ref "U3") (pin "9") (pinfunction "VDDANA_9") (pintype "power_in"))
    )
    (net (code "49") (name "VIN") (class "Default")
      (node (ref "C1") (pin "P$1") (pinfunction "1_P$1") (pintype "passive"))
      (node (ref "J1") (pin "1") (pinfunction "5V_1") (pintype "passive"))
      (node (ref "J2") (pin "3") (pinfunction "P$3_3") (pintype "bidirectional"))
      (node (ref "TP9") (pin "P$1") (pinfunction "P$1_P$1") (pintype "input"))
      (node (ref "U2") (pin "3") (pinfunction "VIN_3") (pintype "input"))
    )
    (net (code "50") (name "unconnected-(J1-ID-Pad4)") (class "Default")
      (node (ref "J1") (pin "4") (pinfunction "ID_4") (pintype "passive"))
    )
    (net (code "51") (name "unconnected-(U3-PA14-Pad15)") (class "Default")
      (node (ref "U3") (pin "15") (pinfunction "PA14_15") (pintype "bidirectional"))
    )
    (net (code "52") (name "unconnected-(U3-PA15-Pad16)") (class "Default")
      (node (ref "U3") (pin "16") (pinfunction "PA15_16") (pintype "bidirectional"))
    )
  )
)
